# untitled11111.net
KiCad netlist of a schematic drawn in EAGLE
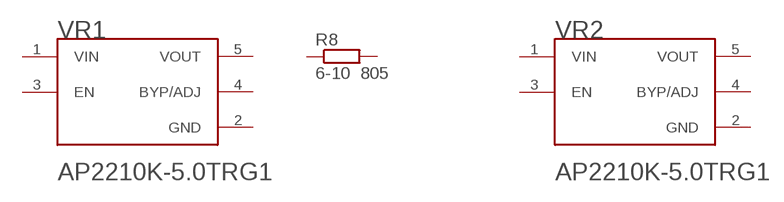
[diagram p0: schematic, sheet 1, part 1 of 2]
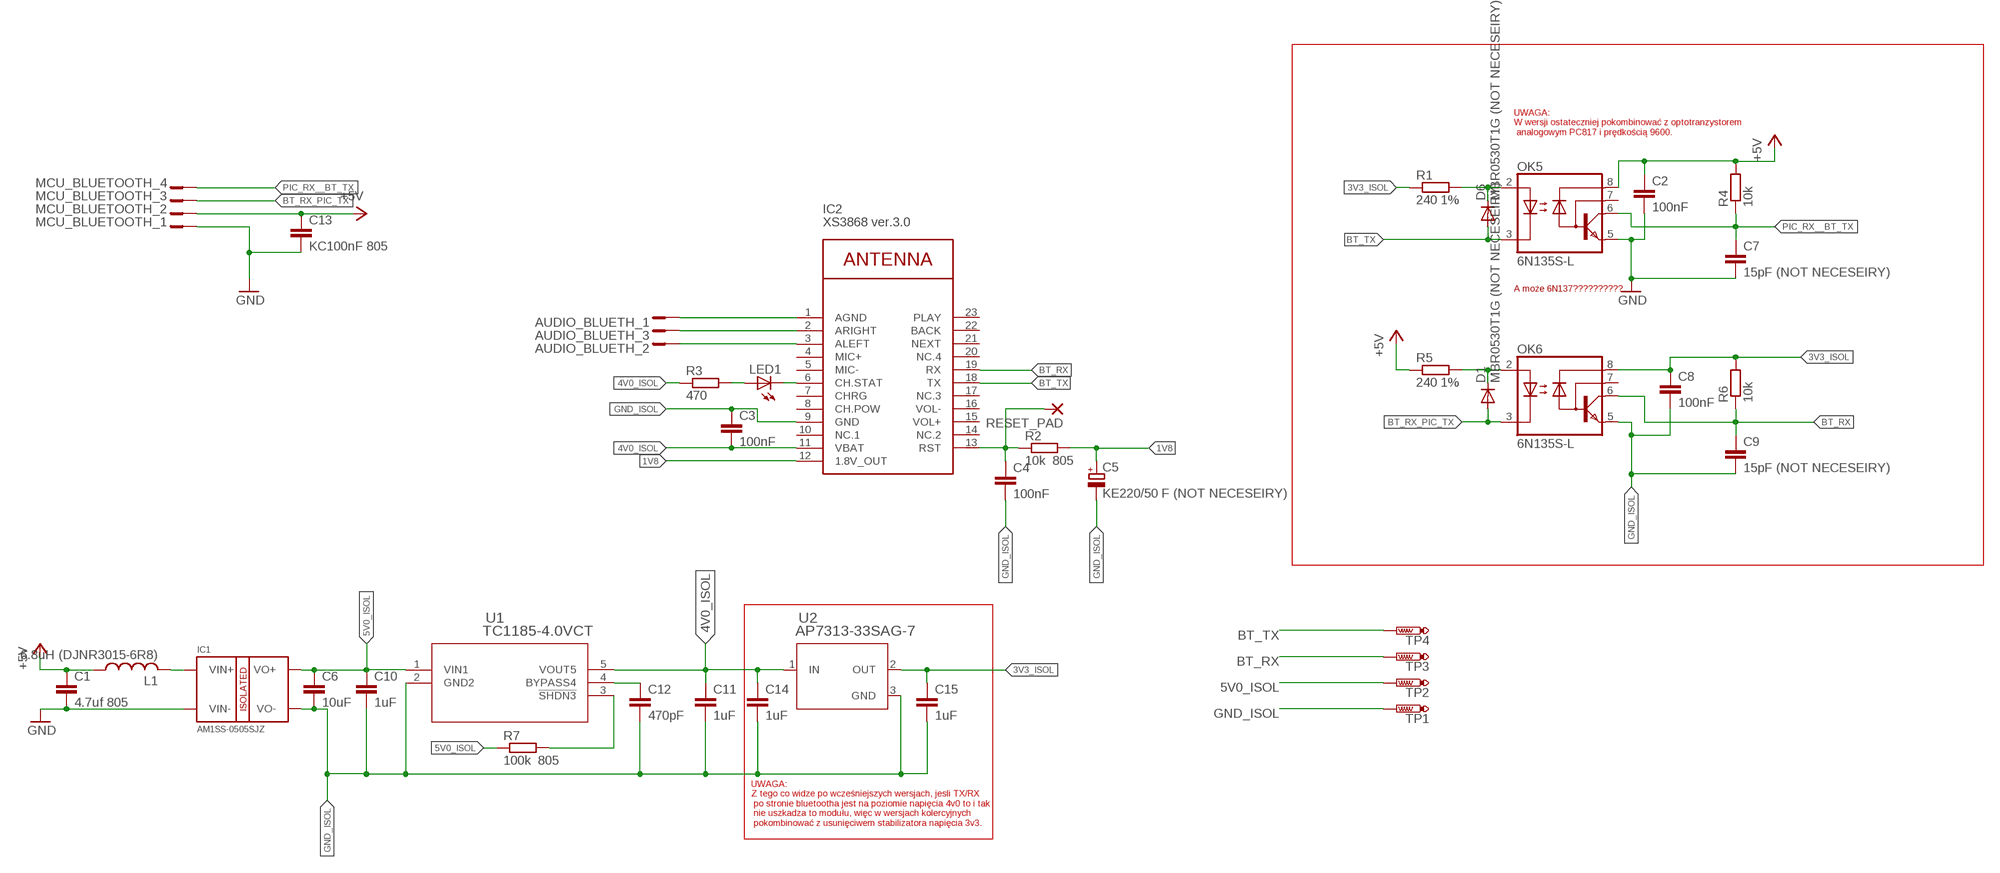
[diagram p1: schematic, sheet 1, part 2 of 2]

(export (version "E")
  (design (tool "Eeschema 10.0.6"))
  (components
    (comp (ref "AUDIO_BLUETH")
      (value "JST_3_PIN_B3B-PH-KS")
      (footprint "eagle-import:B3B-PH-KS")
      (libsource (lib "eagle-import") (part "JST_3_PIN_B3B-PH-KS"))
    )
    (comp (ref "C1")
      (value "4.7uf 805")
      (footprint "eagle-import:C0805")
      (libsource (lib "eagle-import") (part "C-EUC0805"))
    )
    (comp (ref "C2")
      (value "100nF")
      (footprint "eagle-import:C0805")
      (libsource (lib "eagle-import") (part "resistor_C-EUC0805"))
    )
    (comp (ref "C3")
      (value "100nF")
      (footprint "eagle-import:C0805")
      (libsource (lib "eagle-import") (part "resistor_C-EUC0805"))
    )
    (comp (ref "C4")
      (value "100nF")
      (footprint "eagle-import:C0805")
      (libsource (lib "eagle-import") (part "resistor_C-EUC0805"))
    )
    (comp (ref "C5")
      (value "KE220/50 F (NOT NECESEIRY)")
      (footprint "eagle-import:PANASONIC_G")
      (libsource (lib "eagle-import") (part "CPOL-EUG"))
    )
    (comp (ref "C6")
      (value "10uF")
      (footprint "eagle-import:C0805")
      (libsource (lib "eagle-import") (part "resistor_C-EUC0805"))
    )
    (comp (ref "C7")
      (value "15pF (NOT NECESEIRY)")
      (footprint "eagle-import:C0805")
      (libsource (lib "eagle-import") (part "resistor_C-EUC0805"))
    )
    (comp (ref "C8")
      (value "100nF")
      (footprint "eagle-import:C0805")
      (libsource (lib "eagle-import") (part "resistor_C-EUC0805"))
    )
    (comp (ref "C9")
      (value "15pF (NOT NECESEIRY)")
      (footprint "eagle-import:C0805")
      (libsource (lib "eagle-import") (part "resistor_C-EUC0805"))
    )
    (comp (ref "C10")
      (value "1uF")
      (footprint "eagle-import:C0805")
      (libsource (lib "eagle-import") (part "resistor_C-EUC0805"))
    )
    (comp (ref "C11")
      (value "1uF")
      (footprint "eagle-import:C0805")
      (libsource (lib "eagle-import") (part "resistor_C-EUC0805"))
    )
    (comp (ref "C12")
      (value "470pF")
      (footprint "eagle-import:C0805")
      (libsource (lib "eagle-import") (part "resistor_C-EUC0805"))
    )
    (comp (ref "C13")
      (value "KC100nF 805")
      (footprint "eagle-import:C0805")
      (libsource (lib "eagle-import") (part "C-EUC0805"))
    )
    (comp (ref "C14")
      (value "1uF")
      (footprint "eagle-import:C0805")
      (libsource (lib "eagle-import") (part "resistor_C-EUC0805"))
    )
    (comp (ref "C15")
      (value "1uF")
      (footprint "eagle-import:C0805")
      (libsource (lib "eagle-import") (part "resistor_C-EUC0805"))
    )
    (comp (ref "D1")
      (value "MBR0530T1G (NOT NECESEIRY)")
      (footprint "eagle-import:SOD123")
      (libsource (lib "eagle-import") (part "MBR0520LT"))
    )
    (comp (ref "D6")
      (value "MBR0530T1G (NOT NECESEIRY)")
      (footprint "eagle-import:SOD123")
      (libsource (lib "eagle-import") (part "MBR0520LT"))
    )
    (comp (ref "IC1")
      (value "AM1SS-0505SJZ")
      (footprint "eagle-import:SIP4")
      (libsource (lib "eagle-import") (part "AM1SS-0503S-NZ"))
    )
    (comp (ref "IC2")
      (value "XS3868 ver.3.0")
      (footprint "eagle-import:WIRELESS-BLUETOOTH-XS3868")
      (libsource (lib "eagle-import") (part "WIRELESS-BLUETOOTH-XS3868"))
    )
    (comp (ref "L1")
      (value "6.8uH (DJNR3015-6R8)")
      (footprint "eagle-import:L3230M")
      (libsource (lib "eagle-import") (part "L-USL3230M"))
    )
    (comp (ref "LED1")
      (value "LEDSMART-LED")
      (footprint "eagle-import:SMART-LED")
      (libsource (lib "eagle-import") (part "LEDSMART-LED"))
    )
    (comp (ref "MCU_BLUETOOTH")
      (value "JST_4_PIN_B4B-PH-KS")
      (footprint "eagle-import:B4B-PH-KS")
      (libsource (lib "eagle-import") (part "JST_4_PIN_B4B-PH-KS"))
    )
    (comp (ref "OK5")
      (value "6N135S-L")
      (footprint "eagle-import:DIL8-SMD")
      (libsource (lib "eagle-import") (part "6N135DIL8-SMD"))
    )
    (comp (ref "OK6")
      (value "6N135S-L")
      (footprint "eagle-import:DIL8-SMD")
      (libsource (lib "eagle-import") (part "6N135DIL8-SMD"))
    )
    (comp (ref "R1")
      (value "240 1%")
      (footprint "eagle-import:M0805")
      (libsource (lib "eagle-import") (part "R-EU_M0805"))
    )
    (comp (ref "R2")
      (value "10k 805")
      (footprint "eagle-import:M0805")
      (libsource (lib "eagle-import") (part "R-EU_M0805"))
    )
    (comp (ref "R3")
      (value "470")
      (footprint "eagle-import:M0805")
      (libsource (lib "eagle-import") (part "R-EU_M0805"))
    )
    (comp (ref "R4")
      (value "10k")
      (footprint "eagle-import:M0805")
      (libsource (lib "eagle-import") (part "R-EU_M0805"))
    )
    (comp (ref "R5")
      (value "240 1%")
      (footprint "eagle-import:M0805")
      (libsource (lib "eagle-import") (part "R-EU_M0805"))
    )
    (comp (ref "R6")
      (value "10k")
      (footprint "eagle-import:M0805")
      (libsource (lib "eagle-import") (part "R-EU_M0805"))
    )
    (comp (ref "R7")
      (value "100k 805")
      (footprint "eagle-import:M0805")
      (libsource (lib "eagle-import") (part "R-EU_M0805"))
    )
    (comp (ref "R8")
      (value "6-10 805")
      (footprint "eagle-import:M0805")
      (libsource (lib "eagle-import") (part "R-EU_M0805"))
    )
    (comp (ref "RESET_PAD")
      (value "SMD2")
      (footprint "eagle-import:SMD1,27-2,54")
      (libsource (lib "eagle-import") (part "SMD2"))
    )
    (comp (ref "TP1")
      (value "PTR1B1,27")
      (footprint "eagle-import:B1,27")
      (libsource (lib "eagle-import") (part "PTR1B1,27"))
    )
    (comp (ref "TP2")
      (value "PTR1B1,27")
      (footprint "eagle-import:B1,27")
      (libsource (lib "eagle-import") (part "PTR1B1,27"))
    )
    (comp (ref "TP3")
      (value "PTR1B1,27")
      (footprint "eagle-import:B1,27")
      (libsource (lib "eagle-import") (part "PTR1B1,27"))
    )
    (comp (ref "TP4")
      (value "PTR1B1,27")
      (footprint "eagle-import:B1,27")
      (libsource (lib "eagle-import") (part "PTR1B1,27"))
    )
    (comp (ref "U1")
      (value "TC1185-4.0VCT")
      (footprint "eagle-import:SOT-23-5_MC-M")
      (fields (field (name "MANUFACTURER_PART_NUMBER") "TC1185X.XXCT713"))
      (libsource (lib "eagle-import") (part "TC1185-X.XXCT713SOT-23-5_MC-M"))
    )
    (comp (ref "U2")
      (value "AP7313-33SAG-7")
      (footprint "eagle-import:SOT-23")
      (fields (field (name "MANUFACTURER_PART_NUMBER") "AP731333SAG7"))
      (libsource (lib "eagle-import") (part "AP7313-33SAG-7"))
    )
    (comp (ref "VR1")
      (value "DIODES_AP2210K-5.0TRG1DIODES_AP2210K-5.0TRG1_0_0")
      (footprint "eagle-import:DIODES_AP2210K-5.0TRG1_0")
      (fields
        (field (name "DIGIKEY_PART_NUMBER") "AP2210K-5.0TRG1DICT-ND")
        (field (name "MF") "Diodes")
        (field (name "MOUSER_PART_NUMBER") "621-AP2210K-5.0TRG1")
      )
      (libsource (lib "eagle-import") (part "DIODES_AP2210K-5.0TRG1DIODES_AP2210K-5.0TRG1_0_0"))
    )
    (comp (ref "VR2")
      (value "DIODES_AP2210K-5.0TRG1DIODES_AP2210K-5.0TRG1_0_0")
      (footprint "eagle-import:DIODES_AP2210K-5.0TRG1_0")
      (fields
        (field (name "DIGIKEY_PART_NUMBER") "AP2210K-5.0TRG1DICT-ND")
        (field (name "MF") "Diodes")
        (field (name "MOUSER_PART_NUMBER") "621-AP2210K-5.0TRG1")
      )
      (libsource (lib "eagle-import") (part "DIODES_AP2210K-5.0TRG1DIODES_AP2210K-5.0TRG1_0_0"))
    )
  )
  (nets
    (net (code "1") (name "+5V") (class "Default")
      (node (ref "C1") (pin "1") (pinfunction "1_1") (pintype "passive"))
      (node (ref "C13") (pin "1") (pinfunction "1_1") (pintype "passive"))
      (node (ref "C2") (pin "1") (pinfunction "1_1") (pintype "passive"))
      (node (ref "L1") (pin "1") (pinfunction "1_1") (pintype "passive"))
      (node (ref "MCU_BLUETOOTH") (pin "P$2") (pinfunction "P$1_P$2") (pintype "bidirectional"))
      (node (ref "OK5") (pin "8") (pinfunction "VCC_8") (pintype "passive"))
      (node (ref "R4") (pin "2") (pinfunction "2_2") (pintype "passive"))
      (node (ref "R5") (pin "1") (pinfunction "1_1") (pintype "passive"))
    )
    (net (code "2") (name "1V8") (class "Default")
      (node (ref "C5") (pin "+") (pinfunction "+_+") (pintype "passive"))
      (node (ref "IC2") (pin "12") (pinfunction "1.8V_OUT_12") (pintype "power_in"))
      (node (ref "R2") (pin "2") (pinfunction "2_2") (pintype "passive"))
    )
    (net (code "3") (name "3V3_ISOL") (class "Default")
      (node (ref "C15") (pin "1") (pinfunction "1_1") (pintype "passive"))
      (node (ref "C8") (pin "1") (pinfunction "1_1") (pintype "passive"))
      (node (ref "OK6") (pin "8") (pinfunction "VCC_8") (pintype "passive"))
      (node (ref "R1") (pin "1") (pinfunction "1_1") (pintype "passive"))
      (node (ref "R6") (pin "2") (pinfunction "2_2") (pintype "passive"))
      (node (ref "U2") (pin "2") (pinfunction "OUT_2") (pintype "output"))
    )
    (net (code "4") (name "4V0_ISOL") (class "Default")
      (node (ref "C11") (pin "1") (pinfunction "1_1") (pintype "passive"))
      (node (ref "C14") (pin "1") (pinfunction "1_1") (pintype "passive"))
      (node (ref "C3") (pin "2") (pinfunction "2_2") (pintype "passive"))
      (node (ref "IC2") (pin "11") (pinfunction "VBAT_11") (pintype "power_in"))
      (node (ref "R3") (pin "1") (pinfunction "1_1") (pintype "passive"))
      (node (ref "U1") (pin "5") (pinfunction "VOUT5_5") (pintype "passive"))
      (node (ref "U2") (pin "1") (pinfunction "IN_1") (pintype "input"))
    )
    (net (code "5") (name "5V0_ISOL") (class "Default")
      (node (ref "C10") (pin "1") (pinfunction "1_1") (pintype "passive"))
      (node (ref "C6") (pin "1") (pinfunction "1_1") (pintype "passive"))
      (node (ref "IC1") (pin "P$4") (pinfunction "VO+_P$4") (pintype "bidirectional"))
      (node (ref "R7") (pin "1") (pinfunction "1_1") (pintype "passive"))
      (node (ref "TP2") (pin "TP") (pinfunction "TP_TP") (pintype "input"))
      (node (ref "U1") (pin "1") (pinfunction "VIN1_1") (pintype "passive"))
    )
    (net (code "6") (name "BT_RX") (class "Default")
      (node (ref "C9") (pin "1") (pinfunction "1_1") (pintype "passive"))
      (node (ref "IC2") (pin "19") (pinfunction "RX_19") (pintype "bidirectional"))
      (node (ref "OK6") (pin "6") (pinfunction "VO_6") (pintype "passive"))
      (node (ref "R6") (pin "1") (pinfunction "1_1") (pintype "passive"))
      (node (ref "TP3") (pin "TP") (pinfunction "TP_TP") (pintype "input"))
    )
    (net (code "7") (name "BT_RX_PIC_TX") (class "Default")
      (node (ref "D1") (pin "A") (pinfunction "A_A") (pintype "passive"))
      (node (ref "MCU_BLUETOOTH") (pin "P$3") (pinfunction "P$1_P$3") (pintype "bidirectional"))
      (node (ref "OK6") (pin "3") (pinfunction "C_3") (pintype "passive"))
    )
    (net (code "8") (name "BT_TX") (class "Default")
      (node (ref "D6") (pin "A") (pinfunction "A_A") (pintype "passive"))
      (node (ref "IC2") (pin "18") (pinfunction "TX_18") (pintype "bidirectional"))
      (node (ref "OK5") (pin "3") (pinfunction "C_3") (pintype "passive"))
      (node (ref "TP4") (pin "TP") (pinfunction "TP_TP") (pintype "input"))
    )
    (net (code "9") (name "GND") (class "Default")
      (node (ref "C1") (pin "2") (pinfunction "2_2") (pintype "passive"))
      (node (ref "C13") (pin "2") (pinfunction "2_2") (pintype "passive"))
      (node (ref "C2") (pin "2") (pinfunction "2_2") (pintype "passive"))
      (node (ref "C7") (pin "2") (pinfunction "2_2") (pintype "passive"))
      (node (ref "IC1") (pin "P$1") (pinfunction "VIN-_P$1") (pintype "bidirectional"))
      (node (ref "MCU_BLUETOOTH") (pin "P$1") (pinfunction "P$1_P$1") (pintype "bidirectional"))
      (node (ref "OK5") (pin "5") (pinfunction "GND_5") (pintype "passive"))
    )
    (net (code "10") (name "GND_ISOL") (class "Default")
      (node (ref "C10") (pin "2") (pinfunction "2_2") (pintype "passive"))
      (node (ref "C11") (pin "2") (pinfunction "2_2") (pintype "passive"))
      (node (ref "C12") (pin "2") (pinfunction "2_2") (pintype "passive"))
      (node (ref "C14") (pin "2") (pinfunction "2_2") (pintype "passive"))
      (node (ref "C15") (pin "2") (pinfunction "2_2") (pintype "passive"))
      (node (ref "C3") (pin "1") (pinfunction "1_1") (pintype "passive"))
      (node (ref "C4") (pin "2") (pinfunction "2_2") (pintype "passive"))
      (node (ref "C5") (pin "-") (pinfunction "-_-") (pintype "passive"))
      (node (ref "C6") (pin "2") (pinfunction "2_2") (pintype "passive"))
      (node (ref "C8") (pin "2") (pinfunction "2_2") (pintype "passive"))
      (node (ref "C9") (pin "2") (pinfunction "2_2") (pintype "passive"))
      (node (ref "IC1") (pin "P$3") (pinfunction "VO-_P$3") (pintype "bidirectional"))
      (node (ref "IC2") (pin "9") (pinfunction "GND_9") (pintype "power_in"))
      (node (ref "OK6") (pin "5") (pinfunction "GND_5") (pintype "passive"))
      (node (ref "TP1") (pin "TP") (pinfunction "TP_TP") (pintype "input"))
      (node (ref "U1") (pin "2") (pinfunction "GND2_2") (pintype "passive"))
      (node (ref "U2") (pin "3") (pinfunction "GND_3") (pintype "power_in"))
    )
    (net (code "11") (name "Net-(AUDIO_BLUETHB-P$1)") (class "Default")
      (node (ref "AUDIO_BLUETH") (pin "P$2") (pinfunction "P$1_P$2") (pintype "bidirectional"))
      (node (ref "IC2") (pin "3") (pinfunction "ALEFT_3") (pintype "output"))
    )
    (net (code "12") (name "Net-(AUDIO_BLUETHC-P$1)") (class "Default")
      (node (ref "AUDIO_BLUETH") (pin "P$3") (pinfunction "P$1_P$3") (pintype "bidirectional"))
      (node (ref "IC2") (pin "2") (pinfunction "ARIGHT_2") (pintype "output"))
    )
    (net (code "13") (name "Net-(IC1-VIN+)") (class "Default")
      (node (ref "IC1") (pin "P$2") (pinfunction "VIN+_P$2") (pintype "bidirectional"))
      (node (ref "L1") (pin "2") (pinfunction "2_2") (pintype "passive"))
    )
    (net (code "14") (name "Net-(IC2-AGND)") (class "Default")
      (node (ref "AUDIO_BLUETH") (pin "P$1") (pinfunction "P$1_P$1") (pintype "bidirectional"))
      (node (ref "IC2") (pin "1") (pinfunction "AGND_1") (pintype "power_in"))
    )
    (net (code "15") (name "Net-(IC2-CH.STAT)") (class "Default")
      (node (ref "IC2") (pin "6") (pinfunction "CH.STAT_6") (pintype "bidirectional"))
      (node (ref "LED1") (pin "B") (pinfunction "C_B") (pintype "passive"))
    )
    (net (code "16") (name "Net-(IC2-RST)") (class "Default")
      (node (ref "C4") (pin "1") (pinfunction "1_1") (pintype "passive"))
      (node (ref "IC2") (pin "13") (pinfunction "RST_13") (pintype "power_in"))
      (node (ref "R2") (pin "1") (pinfunction "1_1") (pintype "passive"))
      (node (ref "RESET_PAD") (pin "1") (pinfunction "P_1") (pintype "passive"))
    )
    (net (code "17") (name "Net-(LED1-PadA)") (class "Default")
      (node (ref "LED1") (pin "A") (pinfunction "A_A") (pintype "passive"))
      (node (ref "R3") (pin "2") (pinfunction "2_2") (pintype "passive"))
    )
    (net (code "18") (name "Net-(OK5-A)") (class "Default")
      (node (ref "D6") (pin "C") (pinfunction "C_C") (pintype "passive"))
      (node (ref "OK5") (pin "2") (pinfunction "A_2") (pintype "passive"))
      (node (ref "R1") (pin "2") (pinfunction "2_2") (pintype "passive"))
    )
    (net (code "19") (name "Net-(OK6-A)") (class "Default")
      (node (ref "D1") (pin "C") (pinfunction "C_C") (pintype "passive"))
      (node (ref "OK6") (pin "2") (pinfunction "A_2") (pintype "passive"))
      (node (ref "R5") (pin "2") (pinfunction "2_2") (pintype "passive"))
    )
    (net (code "20") (name "Net-(U1-BYPASS4)") (class "Default")
      (node (ref "C12") (pin "1") (pinfunction "1_1") (pintype "passive"))
      (node (ref "U1") (pin "4") (pinfunction "BYPASS4_4") (pintype "passive"))
    )
    (net (code "21") (name "Net-(U1-~{SHDN3})") (class "Default")
      (node (ref "R7") (pin "2") (pinfunction "2_2") (pintype "passive"))
      (node (ref "U1") (pin "3") (pinfunction "~{SHDN3}_3") (pintype "passive"))
    )
    (net (code "22") (name "PIC_RX__BT_TX") (class "Default")
      (node (ref "C7") (pin "1") (pinfunction "1_1") (pintype "passive"))
      (node (ref "MCU_BLUETOOTH") (pin "P$4") (pinfunction "P$1_P$4") (pintype "bidirectional"))
      (node (ref "OK5") (pin "6") (pinfunction "VO_6") (pintype "passive"))
      (node (ref "R4") (pin "1") (pinfunction "1_1") (pintype "passive"))
    )
    (net (code "23") (name "unconnected-(IC2-BACK-Pad22)") (class "Default")
      (node (ref "IC2") (pin "22") (pinfunction "BACK_22") (pintype "bidirectional"))
    )
    (net (code "24") (name "unconnected-(IC2-CH.POW-Pad8)") (class "Default")
      (node (ref "IC2") (pin "8") (pinfunction "CH.POW_8") (pintype "bidirectional"))
    )
    (net (code "25") (name "unconnected-(IC2-CHRG-Pad7)") (class "Default")
      (node (ref "IC2") (pin "7") (pinfunction "CHRG_7") (pintype "bidirectional"))
    )
    (net (code "26") (name "unconnected-(IC2-MIC+-Pad4)") (class "Default")
      (node (ref "IC2") (pin "4") (pinfunction "MIC+_4") (pintype "bidirectional"))
    )
    (net (code "27") (name "unconnected-(IC2-MIC--Pad5)") (class "Default")
      (node (ref "IC2") (pin "5") (pinfunction "MIC-_5") (pintype "bidirectional"))
    )
    (net (code "28") (name "unconnected-(IC2-NC.1-Pad10)") (class "Default")
      (node (ref "IC2") (pin "10") (pinfunction "NC.1_10") (pintype "passive"))
    )
    (net (code "29") (name "unconnected-(IC2-NC.2-Pad14)") (class "Default")
      (node (ref "IC2") (pin "14") (pinfunction "NC.2_14") (pintype "passive"))
    )
    (net (code "30") (name "unconnected-(IC2-NC.3-Pad17)") (class "Default")
      (node (ref "IC2") (pin "17") (pinfunction "NC.3_17") (pintype "passive"))
    )
    (net (code "31") (name "unconnected-(IC2-NC.4-Pad20)") (class "Default")
      (node (ref "IC2") (pin "20") (pinfunction "NC.4_20") (pintype "passive"))
    )
    (net (code "32") (name "unconnected-(IC2-NEXT-Pad21)") (class "Default")
      (node (ref "IC2") (pin "21") (pinfunction "NEXT_21") (pintype "bidirectional"))
    )
    (net (code "33") (name "unconnected-(IC2-PLAY-Pad23)") (class "Default")
      (node (ref "IC2") (pin "23") (pinfunction "PLAY_23") (pintype "bidirectional"))
    )
    (net (code "34") (name "unconnected-(IC2-VOL+-Pad15)") (class "Default")
      (node (ref "IC2") (pin "15") (pinfunction "VOL+_15") (pintype "bidirectional"))
    )
    (net (code "35") (name "unconnected-(IC2-VOL--Pad16)") (class "Default")
      (node (ref "IC2") (pin "16") (pinfunction "VOL-_16") (pintype "bidirectional"))
    )
    (net (code "36") (name "unconnected-(OK5-VB-Pad7)") (class "Default")
      (node (ref "OK5") (pin "7") (pinfunction "VB_7") (pintype "passive"))
    )
    (net (code "37") (name "unconnected-(OK6-VB-Pad7)") (class "Default")
      (node (ref "OK6") (pin "7") (pinfunction "VB_7") (pintype "passive"))
    )
    (net (code "38") (name "unconnected-(R8-Pad1)") (class "Default")
      (node (ref "R8") (pin "1") (pinfunction "1_1") (pintype "passive"))
    )
    (net (code "39") (name "unconnected-(R8-Pad2)") (class "Default")
      (node (ref "R8") (pin "2") (pinfunction "2_2") (pintype "passive"))
    )
    (net (code "40") (name "unconnected-(VR1-BYP{slash}ADJ-Pad4)") (class "Default")
      (node (ref "VR1") (pin "4") (pinfunction "BYP/ADJ_4") (pintype "bidirectional"))
    )
    (net (code "41") (name "unconnected-(VR1-EN-Pad3)") (class "Default")
      (node (ref "VR1") (pin "3") (pinfunction "EN_3") (pintype "bidirectional"))
    )
    (net (code "42") (name "unconnected-(VR1-GND-Pad2)") (class "Default")
      (node (ref "VR1") (pin "2") (pinfunction "GND_2") (pintype "bidirectional"))
    )
    (net (code "43") (name "unconnected-(VR1-VIN-Pad1)") (class "Default")
      (node (ref "VR1") (pin "1") (pinfunction "VIN_1") (pintype "bidirectional"))
    )
    (net (code "44") (name "unconnected-(VR1-VOUT-Pad5)") (class "Default")
      (node (ref "VR1") (pin "5") (pinfunction "VOUT_5") (pintype "bidirectional"))
    )
    (net (code "45") (name "unconnected-(VR2-BYP{slash}ADJ-Pad4)") (class "Default")
      (node (ref "VR2") (pin "4") (pinfunction "BYP/ADJ_4") (pintype "bidirectional"))
    )
    (net (code "46") (name "unconnected-(VR2-EN-Pad3)") (class "Default")
      (node (ref "VR2") (pin "3") (pinfunction "EN_3") (pintype "bidirectional"))
    )
    (net (code "47") (name "unconnected-(VR2-GND-Pad2)") (class "Default")
      (node (ref "VR2") (pin "2") (pinfunction "GND_2") (pintype "bidirectional"))
    )
    (net (code "48") (name "unconnected-(VR2-VIN-Pad1)") (class "Default")
      (node (ref "VR2") (pin "1") (pinfunction "VIN_1") (pintype "bidirectional"))
    )
    (net (code "49") (name "unconnected-(VR2-VOUT-Pad5)") (class "Default")
      (node (ref "VR2") (pin "5") (pinfunction "VOUT_5") (pintype "bidirectional"))
    )
  )
)
